# infra_stlink.net
KiCad netlist of a schematic drawn in Altium Designer
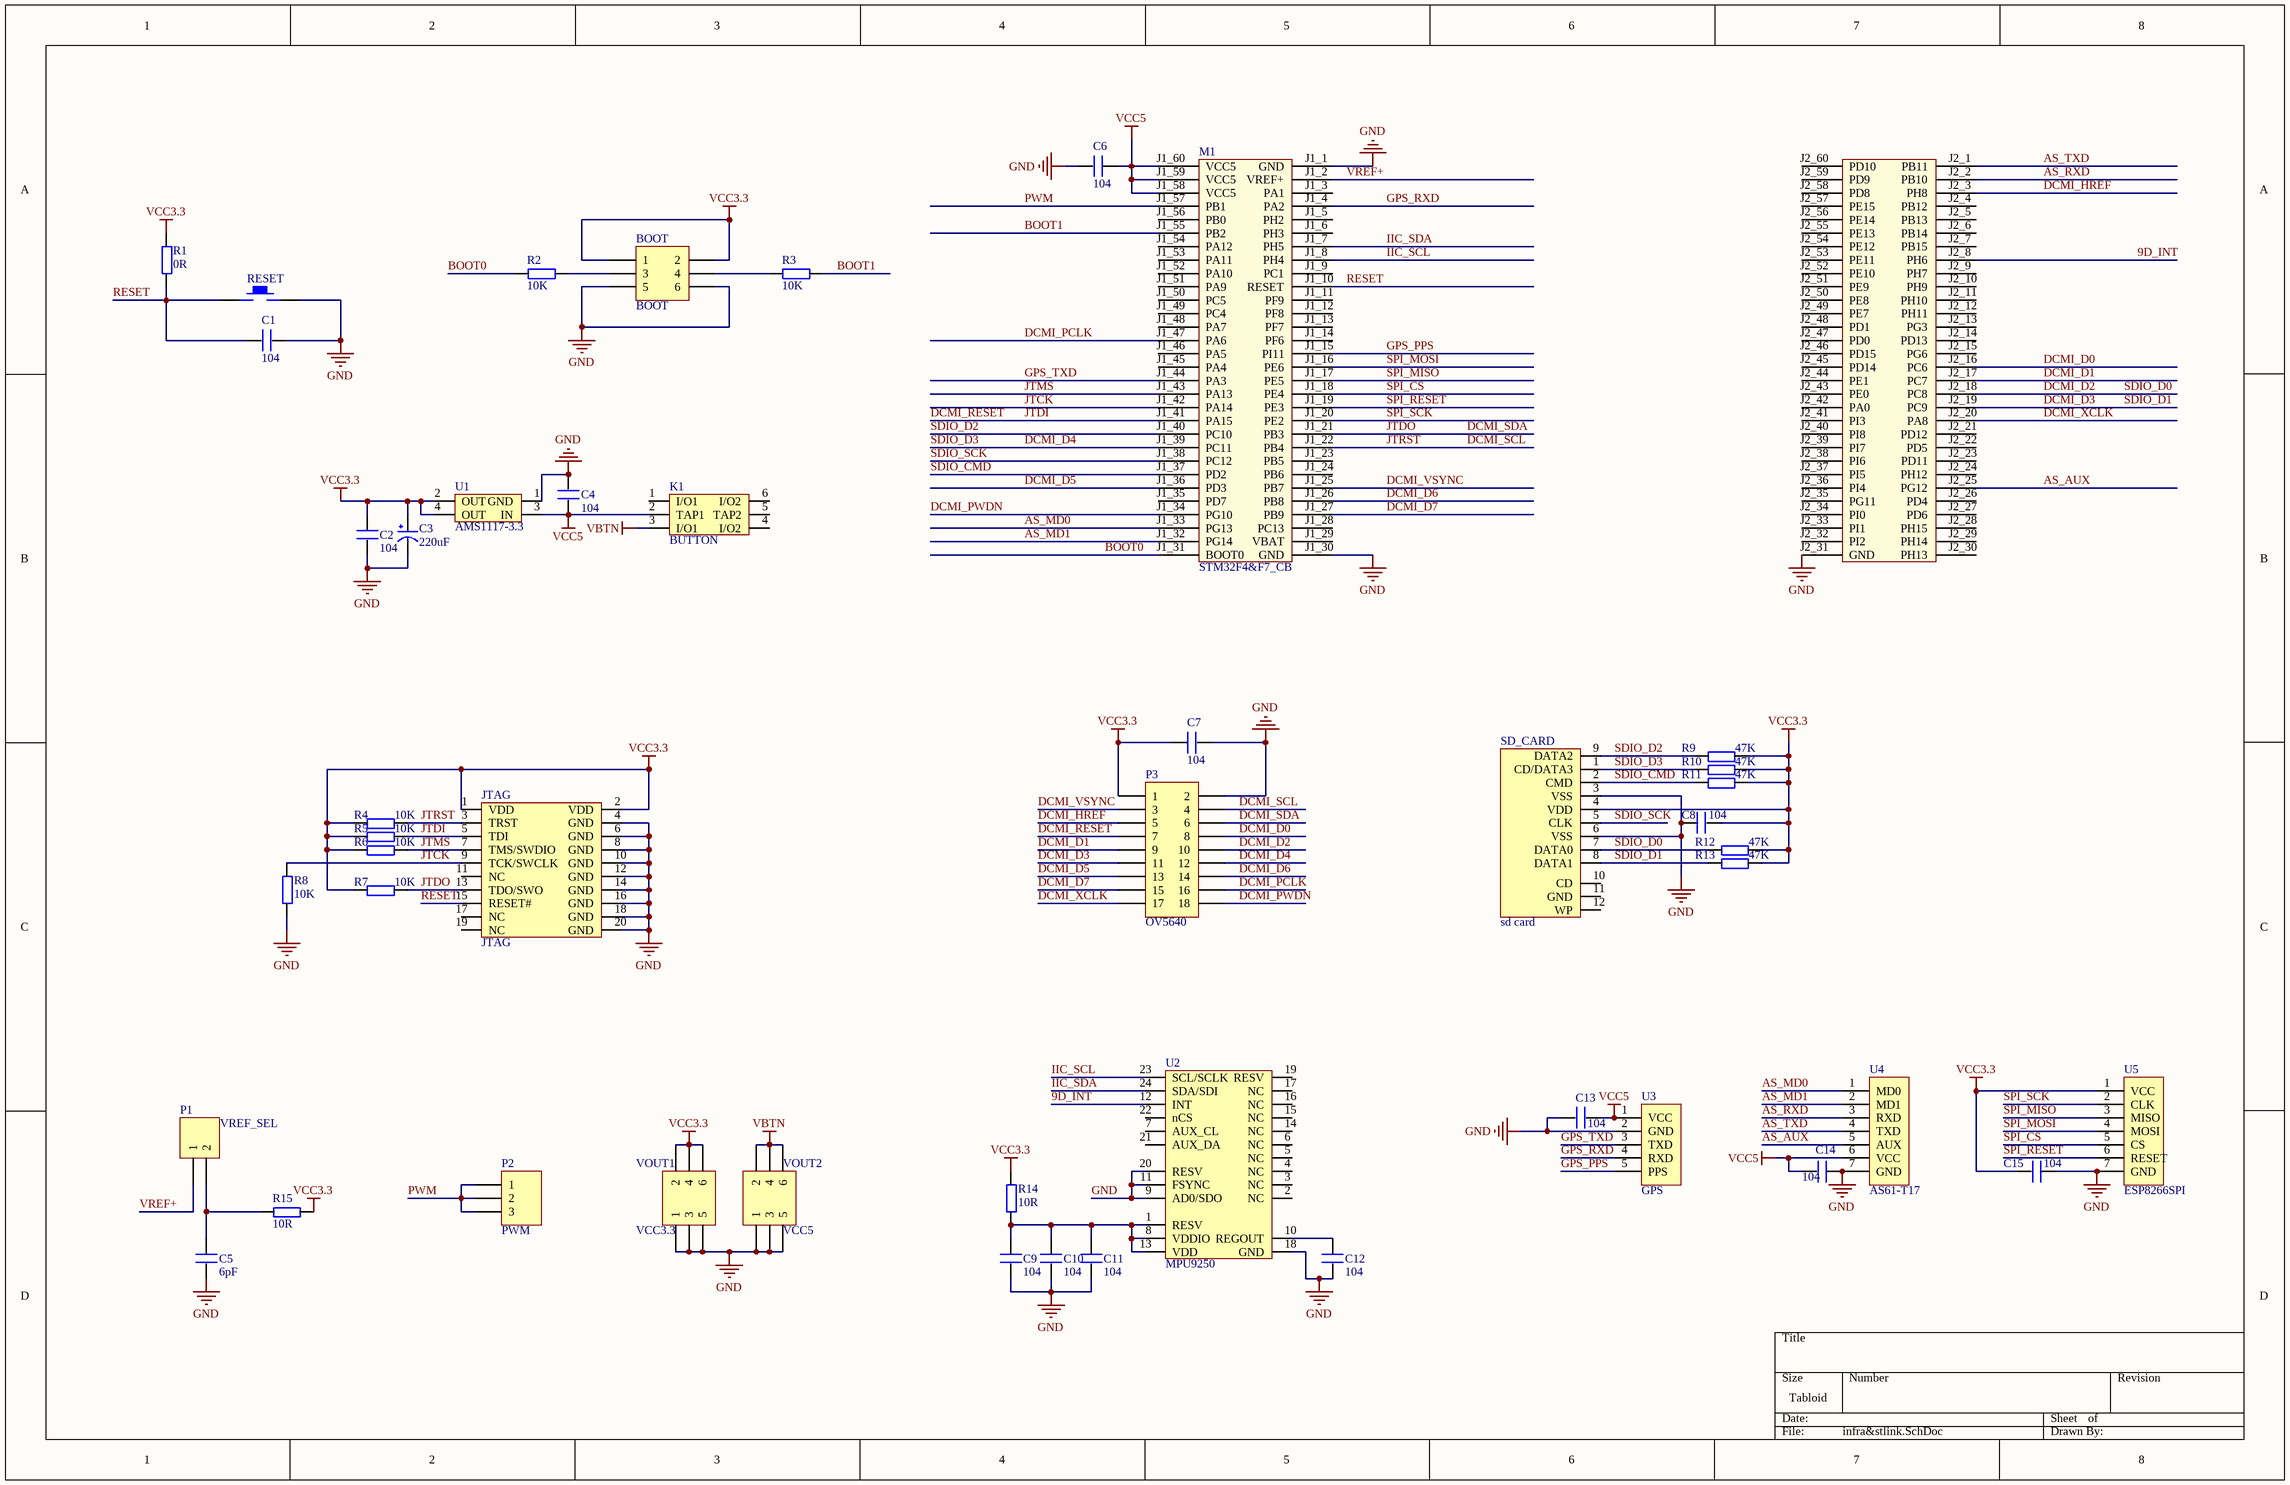
[diagram p0: infra&stlink.SchDoc]

(export (version "E")
  (design (tool "Eeschema 10.0.6"))
  (components
    (comp (ref "BOOT")
      (value "BOOT")
      (footprint "HDR2X3")
      (description "Header, 3-Pin, Dual row")
      (fields (field (name "PUBLISHER") "Altium Limited"))
      (libsource (lib "阿波罗STM32F4&F7底板封装库") (part "Header 3X2"))
    )
    (comp (ref "C1") (value "104") (footprint "0603P") (libsource (lib "阿波罗STM32F4&F7底板封装库") (part "C")))
    (comp (ref "C2") (value "104") (footprint "0805") (libsource (lib "阿波罗STM32F4&F7底板封装库") (part "C")))
    (comp (ref "C3")
      (value "220uF")
      (footprint "CC6.56.5")
      (libsource (lib "阿波罗STM32F4&F7底板封装库") (part "CAP"))
    )
    (comp (ref "C4") (value "104") (footprint "0805") (libsource (lib "阿波罗STM32F4&F7底板封装库") (part "C")))
    (comp (ref "C5") (value "6pF") (footprint "0805") (libsource (lib "STM32F767核心板封装库") (part "C")))
    (comp (ref "C6") (value "104") (footprint "0805") (libsource (lib "阿波罗STM32F4&F7底板封装库") (part "C")))
    (comp (ref "C7") (value "104") (footprint "0805") (libsource (lib "STM32F767核心板封装库") (part "C")))
    (comp (ref "C8") (value "104") (footprint "0805") (libsource (lib "阿波罗STM32F4&F7底板封装库") (part "C")))
    (comp (ref "C9") (value "104") (footprint "0805") (libsource (lib "阿波罗STM32F4&F7底板封装库") (part "C")))
    (comp (ref "C10") (value "104") (footprint "0805") (libsource (lib "阿波罗STM32F4&F7底板封装库") (part "C")))
    (comp (ref "C11") (value "104") (footprint "0805") (libsource (lib "阿波罗STM32F4&F7底板封装库") (part "C")))
    (comp (ref "C12") (value "104") (footprint "0805") (libsource (lib "阿波罗STM32F4&F7底板封装库") (part "C")))
    (comp (ref "C13") (value "104") (footprint "0805") (libsource (lib "阿波罗STM32F4&F7底板封装库") (part "C")))
    (comp (ref "C14") (value "104") (footprint "0805") (libsource (lib "阿波罗STM32F4&F7底板封装库") (part "C")))
    (comp (ref "C15") (value "104") (footprint "0805") (libsource (lib "阿波罗STM32F4&F7底板封装库") (part "C")))
    (comp (ref "JTAG")
      (value "JTAG")
      (footprint "JTAG_20")
      (libsource (lib "阿波罗STM32F4&F7底板封装库") (part "JTAG"))
    )
    (comp (ref "K1")
      (value "BUTTON")
      (footprint "BTN8.5*8.5")
      (libsource (lib "阿波罗STM32F4&F7底板封装库") (part "BUTTON"))
    )
    (comp (ref "M1")
      (value "STM32F4&F7_CB")
      (footprint "STM32F4&F7_CB")
      (description "F429/746 Core Board")
      (libsource (lib "阿波罗STM32F4&F7底板封装库") (part "STM32F4&F7_CB"))
    )
    (comp (ref "P1")
      (value "VREF_SEL")
      (footprint "HDR1X2")
      (description "Header, 2-Pin")
      (fields (field (name "PUBLISHER") "Altium Limited"))
      (libsource (lib "阿波罗STM32F4&F7底板封装库") (part "Header 2"))
    )
    (comp (ref "P2")
      (value "PWM")
      (footprint "HDR1X3")
      (description "Header, 3-Pin")
      (fields (field (name "PUBLISHER") "Altium Limited"))
      (libsource (lib "Miscellaneous Connectors") (part "Header 3"))
    )
    (comp (ref "P3")
      (value "OV5640")
      (footprint "HDR2X9")
      (description "Header, 9-Pin, Dual row")
      (fields (field (name "PUBLISHER") "Altium Limited"))
      (libsource (lib "阿波罗STM32F4&F7底板封装库") (part "Header 9X2"))
    )
    (comp (ref "R1") (value "0R") (footprint "0805") (libsource (lib "STM32F767核心板封装库") (part "R")))
    (comp (ref "R2") (value "10K") (footprint "0805") (libsource (lib "STM32F767核心板封装库") (part "R")))
    (comp (ref "R3") (value "10K") (footprint "0805") (libsource (lib "STM32F767核心板封装库") (part "R")))
    (comp (ref "R4") (value "10K") (footprint "0805") (libsource (lib "STM32F767核心板封装库") (part "R")))
    (comp (ref "R5") (value "10K") (footprint "0805") (libsource (lib "STM32F767核心板封装库") (part "R")))
    (comp (ref "R6") (value "10K") (footprint "0805") (libsource (lib "STM32F767核心板封装库") (part "R")))
    (comp (ref "R7") (value "10K") (footprint "0805") (libsource (lib "STM32F767核心板封装库") (part "R")))
    (comp (ref "R8") (value "10K") (footprint "0805") (libsource (lib "STM32F767核心板封装库") (part "R")))
    (comp (ref "R9") (value "47K") (footprint "0805") (libsource (lib "STM32F767核心板封装库") (part "R")))
    (comp (ref "R10") (value "47K") (footprint "0805") (libsource (lib "STM32F767核心板封装库") (part "R")))
    (comp (ref "R11") (value "47K") (footprint "0805") (libsource (lib "STM32F767核心板封装库") (part "R")))
    (comp (ref "R12") (value "47K") (footprint "0805") (libsource (lib "STM32F767核心板封装库") (part "R")))
    (comp (ref "R13") (value "47K") (footprint "0805") (libsource (lib "STM32F767核心板封装库") (part "R")))
    (comp (ref "R14") (value "10R") (footprint "0805") (libsource (lib "STM32F767核心板封装库") (part "R")))
    (comp (ref "R15") (value "10R") (footprint "0805") (libsource (lib "STM32F767核心板封装库") (part "R")))
    (comp (ref "RESET")
      (value "KEY_M")
      (footprint "KEY_M")
      (libsource (lib "阿波罗STM32F4&F7底板封装库") (part "KEY_M"))
    )
    (comp (ref "SD_CARD")
      (value "sd card")
      (footprint "SDCARD_L")
      (libsource (lib "阿波罗STM32F4&F7底板封装库") (part "sd card"))
    )
    (comp (ref "U1")
      (value "AMS1117-3.3")
      (footprint "AMS1117")
      (libsource (lib "阿波罗STM32F4&F7底板封装库") (part "AMS1117"))
    )
    (comp (ref "U2")
      (value "MPU9250")
      (footprint "QFN24-t")
      (description "9轴运动处理传感器")
      (libsource (lib "阿波罗STM32F4&F7底板封装库") (part "MPU9250"))
    )
    (comp (ref "U3")
      (value "GPS")
      (footprint "HDR1X5")
      (description "Header, 5-Pin")
      (fields (field (name "PUBLISHER") "Altium Limited"))
      (libsource (lib "Miscellaneous Connectors") (part "Header 5"))
    )
    (comp (ref "U4")
      (value "AS61-T17")
      (footprint "HDR1X7")
      (description "Header, 7-Pin")
      (fields (field (name "PUBLISHER") "Altium Limited"))
      (libsource (lib "Miscellaneous Connectors") (part "Header 7"))
    )
    (comp (ref "U5")
      (value "ESP8266SPI")
      (footprint "HDR1X7")
      (description "Header, 7-Pin")
      (fields (field (name "PUBLISHER") "Altium Limited"))
      (libsource (lib "Miscellaneous Connectors") (part "Header 7"))
    )
    (comp (ref "VOUT1")
      (value "VCC3.3")
      (footprint "HDR2X3")
      (description "Header, 3-Pin, Dual row")
      (fields (field (name "PUBLISHER") "Altium Limited"))
      (libsource (lib "Miscellaneous Connectors") (part "Header 3X2"))
    )
    (comp (ref "VOUT2")
      (value "VCC5")
      (footprint "HDR2X3")
      (description "Header, 3-Pin, Dual row")
      (fields (field (name "PUBLISHER") "Altium Limited"))
      (libsource (lib "Miscellaneous Connectors") (part "Header 3X2"))
    )
  )
  (nets
    (net (code "1") (name "/9D_INT") (class "Default")
      (node (ref "M1") (pin "J2_8") (pinfunction "PH6_J2_8") (pintype "passive"))
      (node (ref "U2") (pin "12") (pinfunction "INT_12") (pintype "passive"))
    )
    (net (code "2") (name "/AS_AUX") (class "Default")
      (node (ref "M1") (pin "J2_25") (pinfunction "PG12_J2_25") (pintype "passive"))
      (node (ref "U4") (pin "5") (pinfunction "CS_5") (pintype "passive"))
    )
    (net (code "3") (name "/AS_MD0") (class "Default")
      (node (ref "M1") (pin "J1_33") (pinfunction "PG13_J1_33") (pintype "passive"))
      (node (ref "U4") (pin "1") (pinfunction "VCC_1") (pintype "passive"))
    )
    (net (code "4") (name "/AS_MD1") (class "Default")
      (node (ref "M1") (pin "J1_32") (pinfunction "PG14_J1_32") (pintype "passive"))
      (node (ref "U4") (pin "2") (pinfunction "CLK_2") (pintype "passive"))
    )
    (net (code "5") (name "/AS_RXD") (class "Default")
      (node (ref "M1") (pin "J2_2") (pinfunction "PB10_J2_2") (pintype "passive"))
      (node (ref "U4") (pin "3") (pinfunction "MISO_3") (pintype "passive"))
    )
    (net (code "6") (name "/AS_TXD") (class "Default")
      (node (ref "M1") (pin "J2_1") (pinfunction "PB11_J2_1") (pintype "passive"))
      (node (ref "U4") (pin "4") (pinfunction "MOSI_4") (pintype "passive"))
    )
    (net (code "7") (name "/BOOT0") (class "Default")
      (node (ref "M1") (pin "J1_31") (pinfunction "BOOT0_J1_31") (pintype "passive"))
      (node (ref "R2") (pin "1") (pintype "passive"))
    )
    (net (code "8") (name "/BOOT1") (class "Default")
      (node (ref "M1") (pin "J1_55") (pinfunction "PB2_J1_55") (pintype "passive"))
      (node (ref "R3") (pin "2") (pintype "passive"))
    )
    (net (code "9") (name "/DCMI_D0") (class "Default")
      (node (ref "M1") (pin "J2_16") (pinfunction "PC6_J2_16") (pintype "passive"))
      (node (ref "P3") (pin "8") (pinfunction "8_8") (pintype "passive"))
    )
    (net (code "10") (name "/DCMI_D1") (class "Default")
      (node (ref "M1") (pin "J2_17") (pinfunction "PC7_J2_17") (pintype "passive"))
      (node (ref "P3") (pin "9") (pinfunction "9_9") (pintype "passive"))
    )
    (net (code "11") (name "/DCMI_D2") (class "Default")
      (node (ref "M1") (pin "J2_18") (pinfunction "PC8_J2_18") (pintype "passive"))
      (node (ref "P3") (pin "10") (pinfunction "10_10") (pintype "passive"))
      (node (ref "R12") (pin "1") (pintype "passive"))
      (node (ref "SD_CARD") (pin "7") (pinfunction "DATA0_7") (pintype "passive"))
    )
    (net (code "12") (name "/DCMI_D3") (class "Default")
      (node (ref "M1") (pin "J2_19") (pinfunction "PC9_J2_19") (pintype "passive"))
      (node (ref "P3") (pin "11") (pinfunction "11_11") (pintype "passive"))
      (node (ref "R13") (pin "1") (pintype "passive"))
      (node (ref "SD_CARD") (pin "8") (pinfunction "DATA1_8") (pintype "passive"))
    )
    (net (code "13") (name "/DCMI_D4") (class "Default")
      (node (ref "M1") (pin "J1_39") (pinfunction "PC11_J1_39") (pintype "passive"))
      (node (ref "P3") (pin "12") (pinfunction "12_12") (pintype "passive"))
      (node (ref "R10") (pin "1") (pintype "passive"))
      (node (ref "SD_CARD") (pin "1") (pinfunction "CD/DATA3_1") (pintype "passive"))
    )
    (net (code "14") (name "/DCMI_D5") (class "Default")
      (node (ref "M1") (pin "J1_36") (pinfunction "PD3_J1_36") (pintype "passive"))
      (node (ref "P3") (pin "13") (pinfunction "13_13") (pintype "passive"))
    )
    (net (code "15") (name "/DCMI_D6") (class "Default")
      (node (ref "M1") (pin "J1_26") (pinfunction "PB8_J1_26") (pintype "passive"))
      (node (ref "P3") (pin "14") (pinfunction "14_14") (pintype "passive"))
    )
    (net (code "16") (name "/DCMI_D7") (class "Default")
      (node (ref "M1") (pin "J1_27") (pinfunction "PB9_J1_27") (pintype "passive"))
      (node (ref "P3") (pin "15") (pinfunction "15_15") (pintype "passive"))
    )
    (net (code "17") (name "/DCMI_HREF") (class "Default")
      (node (ref "M1") (pin "J2_3") (pinfunction "PH8_J2_3") (pintype "passive"))
      (node (ref "P3") (pin "5") (pinfunction "5_5") (pintype "passive"))
    )
    (net (code "18") (name "/DCMI_PCLK") (class "Default")
      (node (ref "M1") (pin "J1_47") (pinfunction "PA6_J1_47") (pintype "passive"))
      (node (ref "P3") (pin "16") (pinfunction "16_16") (pintype "passive"))
    )
    (net (code "19") (name "/DCMI_PWDN") (class "Default")
      (node (ref "M1") (pin "J1_34") (pinfunction "PG10_J1_34") (pintype "passive"))
      (node (ref "P3") (pin "18") (pinfunction "18_18") (pintype "passive"))
    )
    (net (code "20") (name "/DCMI_RESET") (class "Default")
      (node (ref "JTAG") (pin "5") (pinfunction "TDI_5") (pintype "passive"))
      (node (ref "M1") (pin "J1_41") (pinfunction "PA15_J1_41") (pintype "passive"))
      (node (ref "P3") (pin "7") (pinfunction "7_7") (pintype "passive"))
      (node (ref "R5") (pin "2") (pintype "passive"))
    )
    (net (code "21") (name "/DCMI_SCL") (class "Default")
      (node (ref "JTAG") (pin "3") (pinfunction "TRST_3") (pintype "passive"))
      (node (ref "M1") (pin "J1_22") (pinfunction "PB4_J1_22") (pintype "passive"))
      (node (ref "P3") (pin "4") (pinfunction "4_4") (pintype "passive"))
      (node (ref "R4") (pin "2") (pintype "passive"))
    )
    (net (code "22") (name "/DCMI_SDA") (class "Default")
      (node (ref "JTAG") (pin "13") (pinfunction "TDO/SWO_13") (pintype "passive"))
      (node (ref "M1") (pin "J1_21") (pinfunction "PB3_J1_21") (pintype "passive"))
      (node (ref "P3") (pin "6") (pinfunction "6_6") (pintype "passive"))
      (node (ref "R7") (pin "2") (pintype "passive"))
    )
    (net (code "23") (name "/DCMI_VSYNC") (class "Default")
      (node (ref "M1") (pin "J1_25") (pinfunction "PB7_J1_25") (pintype "passive"))
      (node (ref "P3") (pin "3") (pinfunction "3_3") (pintype "passive"))
    )
    (net (code "24") (name "/DCMI_XCLK") (class "Default")
      (node (ref "M1") (pin "J2_20") (pinfunction "PA8_J2_20") (pintype "passive"))
      (node (ref "P3") (pin "17") (pinfunction "17_17") (pintype "passive"))
    )
    (net (code "25") (name "/GPS_PPS") (class "Default")
      (node (ref "M1") (pin "J1_15") (pinfunction "PI11_J1_15") (pintype "passive"))
      (node (ref "U3") (pin "5") (pinfunction "PPS_5") (pintype "passive"))
    )
    (net (code "26") (name "/GPS_RXD") (class "Default")
      (node (ref "M1") (pin "J1_4") (pinfunction "PA2_J1_4") (pintype "passive"))
      (node (ref "U3") (pin "4") (pinfunction "RXD_4") (pintype "passive"))
    )
    (net (code "27") (name "/GPS_TXD") (class "Default")
      (node (ref "M1") (pin "J1_44") (pinfunction "PA3_J1_44") (pintype "passive"))
      (node (ref "U3") (pin "3") (pinfunction "TXD_3") (pintype "passive"))
    )
    (net (code "28") (name "/IIC_SCL") (class "Default")
      (node (ref "M1") (pin "J1_8") (pinfunction "PH4_J1_8") (pintype "passive"))
      (node (ref "U2") (pin "23") (pinfunction "SCL/SCLK_23") (pintype "passive"))
    )
    (net (code "29") (name "/IIC_SDA") (class "Default")
      (node (ref "M1") (pin "J1_7") (pinfunction "PH5_J1_7") (pintype "passive"))
      (node (ref "U2") (pin "24") (pinfunction "SDA/SDI_24") (pintype "passive"))
    )
    (net (code "30") (name "/JTCK") (class "Default")
      (node (ref "JTAG") (pin "9") (pinfunction "TCK/SWCLK_9") (pintype "passive"))
      (node (ref "M1") (pin "J1_42") (pinfunction "PA14_J1_42") (pintype "passive"))
      (node (ref "R8") (pin "2") (pintype "passive"))
    )
    (net (code "31") (name "/JTMS") (class "Default")
      (node (ref "JTAG") (pin "7") (pinfunction "TMS/SWDIO_7") (pintype "passive"))
      (node (ref "M1") (pin "J1_43") (pinfunction "PA13_J1_43") (pintype "passive"))
      (node (ref "R6") (pin "2") (pintype "passive"))
    )
    (net (code "32") (name "/PWM") (class "Default")
      (node (ref "M1") (pin "J1_57") (pinfunction "PB1_J1_57") (pintype "passive"))
      (node (ref "P2") (pin "1") (pinfunction "1_1") (pintype "passive"))
      (node (ref "P2") (pin "2") (pinfunction "2_2") (pintype "passive"))
      (node (ref "P2") (pin "3") (pinfunction "3_3") (pintype "passive"))
    )
    (net (code "33") (name "/RESET") (class "Default")
      (node (ref "C1") (pin "1") (pintype "passive"))
      (node (ref "JTAG") (pin "15") (pinfunction "RESET#_15") (pintype "passive"))
      (node (ref "M1") (pin "J1_10") (pinfunction "RESET_J1_10") (pintype "passive"))
      (node (ref "R1") (pin "1") (pintype "passive"))
      (node (ref "RESET") (pin "1") (pinfunction "1_1") (pintype "passive"))
    )
    (net (code "34") (name "/SDIO_CMD") (class "Default")
      (node (ref "M1") (pin "J1_37") (pinfunction "PD2_J1_37") (pintype "passive"))
      (node (ref "R11") (pin "1") (pintype "passive"))
      (node (ref "SD_CARD") (pin "2") (pinfunction "CMD_2") (pintype "passive"))
    )
    (net (code "35") (name "/SDIO_D2") (class "Default")
      (node (ref "M1") (pin "J1_40") (pinfunction "PC10_J1_40") (pintype "passive"))
      (node (ref "R9") (pin "1") (pintype "passive"))
      (node (ref "SD_CARD") (pin "9") (pinfunction "DATA2_9") (pintype "passive"))
    )
    (net (code "36") (name "/SDIO_SCK") (class "Default")
      (node (ref "M1") (pin "J1_38") (pinfunction "PC12_J1_38") (pintype "passive"))
      (node (ref "SD_CARD") (pin "5") (pinfunction "CLK_5") (pintype "passive"))
    )
    (net (code "37") (name "/SPI_CS") (class "Default")
      (node (ref "M1") (pin "J1_18") (pinfunction "PE4_J1_18") (pintype "passive"))
      (node (ref "U5") (pin "5") (pinfunction "CS_5") (pintype "passive"))
    )
    (net (code "38") (name "/SPI_MISO") (class "Default")
      (node (ref "M1") (pin "J1_17") (pinfunction "PE5_J1_17") (pintype "passive"))
      (node (ref "U5") (pin "3") (pinfunction "MISO_3") (pintype "passive"))
    )
    (net (code "39") (name "/SPI_MOSI") (class "Default")
      (node (ref "M1") (pin "J1_16") (pinfunction "PE6_J1_16") (pintype "passive"))
      (node (ref "U5") (pin "4") (pinfunction "MOSI_4") (pintype "passive"))
    )
    (net (code "40") (name "/SPI_RESET") (class "Default")
      (node (ref "M1") (pin "J1_19") (pinfunction "PE3_J1_19") (pintype "passive"))
      (node (ref "U5") (pin "6") (pinfunction "RESET_6") (pintype "passive"))
    )
    (net (code "41") (name "/SPI_SCK") (class "Default")
      (node (ref "M1") (pin "J1_20") (pinfunction "PE2_J1_20") (pintype "passive"))
      (node (ref "U5") (pin "2") (pinfunction "CLK_2") (pintype "passive"))
    )
    (net (code "42") (name "/VREF+") (class "Default")
      (node (ref "M1") (pin "J1_2") (pinfunction "VREF+_J1_2") (pintype "passive"))
      (node (ref "P1") (pin "1") (pinfunction "1_1") (pintype "passive"))
    )
    (net (code "43") (name "GND") (class "Default")
      (node (ref "BOOT") (pin "5") (pinfunction "5_5") (pintype "passive"))
      (node (ref "BOOT") (pin "6") (pinfunction "6_6") (pintype "passive"))
      (node (ref "C1") (pin "2") (pintype "passive"))
      (node (ref "C10") (pin "1") (pintype "passive"))
      (node (ref "C11") (pin "1") (pintype "passive"))
      (node (ref "C12") (pin "1") (pintype "passive"))
      (node (ref "C13") (pin "1") (pintype "passive"))
      (node (ref "C14") (pin "1") (pintype "passive"))
      (node (ref "C15") (pin "2") (pintype "passive"))
      (node (ref "C2") (pin "1") (pintype "passive"))
      (node (ref "C3") (pin "2") (pinfunction "GND_2") (pintype "passive"))
      (node (ref "C4") (pin "2") (pintype "passive"))
      (node (ref "C5") (pin "1") (pintype "passive"))
      (node (ref "C6") (pin "1") (pintype "passive"))
      (node (ref "C7") (pin "2") (pintype "passive"))
      (node (ref "C8") (pin "1") (pintype "passive"))
      (node (ref "C9") (pin "1") (pintype "passive"))
      (node (ref "JTAG") (pin "10") (pinfunction "GND_10") (pintype "passive"))
      (node (ref "JTAG") (pin "12") (pinfunction "GND_12") (pintype "passive"))
      (node (ref "JTAG") (pin "14") (pinfunction "GND_14") (pintype "passive"))
      (node (ref "JTAG") (pin "16") (pinfunction "GND_16") (pintype "passive"))
      (node (ref "JTAG") (pin "18") (pinfunction "GND_18") (pintype "passive"))
      (node (ref "JTAG") (pin "20") (pinfunction "GND_20") (pintype "passive"))
      (node (ref "JTAG") (pin "4") (pinfunction "GND_4") (pintype "passive"))
      (node (ref "JTAG") (pin "6") (pinfunction "GND_6") (pintype "passive"))
      (node (ref "JTAG") (pin "8") (pinfunction "GND_8") (pintype "passive"))
      (node (ref "M1") (pin "J1_1") (pinfunction "GND_J1_1") (pintype "passive"))
      (node (ref "M1") (pin "J1_30") (pinfunction "GND_J1_30") (pintype "passive"))
      (node (ref "M1") (pin "J2_31") (pinfunction "GND_J2_31") (pintype "passive"))
      (node (ref "P3") (pin "2") (pinfunction "2_2") (pintype "passive"))
      (node (ref "R8") (pin "1") (pintype "passive"))
      (node (ref "RESET") (pin "2") (pinfunction "2_2") (pintype "passive"))
      (node (ref "SD_CARD") (pin "3") (pinfunction "VSS_3") (pintype "passive"))
      (node (ref "SD_CARD") (pin "6") (pinfunction "VSS_6") (pintype "passive"))
      (node (ref "U1") (pin "1") (pinfunction "GND_1") (pintype "passive"))
      (node (ref "U2") (pin "11") (pinfunction "FSYNC_11") (pintype "passive"))
      (node (ref "U2") (pin "18") (pinfunction "GND_18") (pintype "passive"))
      (node (ref "U2") (pin "20") (pinfunction "RESV_20") (pintype "passive"))
      (node (ref "U2") (pin "9") (pinfunction "AD0/SDO_9") (pintype "passive"))
      (node (ref "U3") (pin "2") (pinfunction "GND_2") (pintype "passive"))
      (node (ref "U4") (pin "7") (pinfunction "GND_7") (pintype "passive"))
      (node (ref "U5") (pin "7") (pinfunction "GND_7") (pintype "passive"))
      (node (ref "VOUT1") (pin "1") (pinfunction "1_1") (pintype "passive"))
      (node (ref "VOUT1") (pin "3") (pinfunction "3_3") (pintype "passive"))
      (node (ref "VOUT1") (pin "5") (pinfunction "5_5") (pintype "passive"))
      (node (ref "VOUT2") (pin "1") (pinfunction "1_1") (pintype "passive"))
      (node (ref "VOUT2") (pin "3") (pinfunction "3_3") (pintype "passive"))
      (node (ref "VOUT2") (pin "5") (pinfunction "5_5") (pintype "passive"))
    )
    (net (code "44") (name "Net-(BOOT-Pad3)") (class "Default")
      (node (ref "BOOT") (pin "3") (pinfunction "3_3") (pintype "passive"))
      (node (ref "R2") (pin "2") (pintype "passive"))
    )
    (net (code "45") (name "Net-(BOOT-Pad4)") (class "Default")
      (node (ref "BOOT") (pin "4") (pinfunction "4_4") (pintype "passive"))
      (node (ref "R3") (pin "1") (pintype "passive"))
    )
    (net (code "46") (name "Net-(C5-Pad2)") (class "Default")
      (node (ref "C5") (pin "2") (pintype "passive"))
      (node (ref "P1") (pin "2") (pinfunction "2_2") (pintype "passive"))
      (node (ref "R15") (pin "1") (pintype "passive"))
    )
    (net (code "47") (name "Net-(U2-REGOUT)") (class "Default")
      (node (ref "C12") (pin "2") (pintype "passive"))
      (node (ref "U2") (pin "10") (pinfunction "REGOUT_10") (pintype "passive"))
    )
    (net (code "48") (name "Net-(U2-VDD)") (class "Default")
      (node (ref "C10") (pin "2") (pintype "passive"))
      (node (ref "C11") (pin "2") (pintype "passive"))
      (node (ref "C9") (pin "2") (pintype "passive"))
      (node (ref "R14") (pin "1") (pintype "passive"))
      (node (ref "U2") (pin "1") (pinfunction "RESV_1") (pintype "passive"))
      (node (ref "U2") (pin "13") (pinfunction "VDD_13") (pintype "passive"))
      (node (ref "U2") (pin "8") (pinfunction "VDDIO_8") (pintype "passive"))
    )
    (net (code "49") (name "VBTN") (class "Default")
      (node (ref "K1") (pin "3") (pinfunction "I/O1_3") (pintype "passive"))
      (node (ref "VOUT2") (pin "2") (pinfunction "2_2") (pintype "passive"))
      (node (ref "VOUT2") (pin "4") (pinfunction "4_4") (pintype "passive"))
      (node (ref "VOUT2") (pin "6") (pinfunction "6_6") (pintype "passive"))
    )
    (net (code "50") (name "VCC3.3") (class "Default")
      (node (ref "BOOT") (pin "1") (pinfunction "1_1") (pintype "passive"))
      (node (ref "BOOT") (pin "2") (pinfunction "2_2") (pintype "passive"))
      (node (ref "C15") (pin "1") (pintype "passive"))
      (node (ref "C2") (pin "2") (pintype "passive"))
      (node (ref "C3") (pin "1") (pinfunction "VCC_1") (pintype "passive"))
      (node (ref "C7") (pin "1") (pintype "passive"))
      (node (ref "C8") (pin "2") (pintype "passive"))
      (node (ref "JTAG") (pin "1") (pinfunction "VDD_1") (pintype "passive"))
      (node (ref "JTAG") (pin "2") (pinfunction "VDD_2") (pintype "passive"))
      (node (ref "P3") (pin "1") (pinfunction "1_1") (pintype "passive"))
      (node (ref "R1") (pin "2") (pintype "passive"))
      (node (ref "R10") (pin "2") (pintype "passive"))
      (node (ref "R11") (pin "2") (pintype "passive"))
      (node (ref "R12") (pin "2") (pintype "passive"))
      (node (ref "R13") (pin "2") (pintype "passive"))
      (node (ref "R14") (pin "2") (pintype "passive"))
      (node (ref "R15") (pin "2") (pintype "passive"))
      (node (ref "R4") (pin "1") (pintype "passive"))
      (node (ref "R5") (pin "1") (pintype "passive"))
      (node (ref "R6") (pin "1") (pintype "passive"))
      (node (ref "R7") (pin "1") (pintype "passive"))
      (node (ref "R9") (pin "2") (pintype "passive"))
      (node (ref "SD_CARD") (pin "4") (pinfunction "VDD_4") (pintype "passive"))
      (node (ref "U1") (pin "2") (pinfunction "OUT_2") (pintype "passive"))
      (node (ref "U1") (pin "4") (pinfunction "OUT_4") (pintype "passive"))
      (node (ref "U5") (pin "1") (pinfunction "VCC_1") (pintype "passive"))
      (node (ref "VOUT1") (pin "2") (pinfunction "2_2") (pintype "passive"))
      (node (ref "VOUT1") (pin "4") (pinfunction "4_4") (pintype "passive"))
      (node (ref "VOUT1") (pin "6") (pinfunction "6_6") (pintype "passive"))
    )
    (net (code "51") (name "VCC5") (class "Default")
      (node (ref "C13") (pin "2") (pintype "passive"))
      (node (ref "C14") (pin "2") (pintype "passive"))
      (node (ref "C4") (pin "1") (pintype "passive"))
      (node (ref "C6") (pin "2") (pintype "passive"))
      (node (ref "K1") (pin "2") (pinfunction "TAP1_2") (pintype "passive"))
      (node (ref "M1") (pin "J1_58") (pinfunction "VCC5_J1_58") (pintype "passive"))
      (node (ref "M1") (pin "J1_59") (pinfunction "VCC5_J1_59") (pintype "passive"))
      (node (ref "M1") (pin "J1_60") (pinfunction "VCC5_J1_60") (pintype "passive"))
      (node (ref "U1") (pin "3") (pinfunction "IN_3") (pintype "passive"))
      (node (ref "U3") (pin "1") (pinfunction "VCC_1") (pintype "passive"))
      (node (ref "U4") (pin "6") (pinfunction "RESET_6") (pintype "passive"))
    )
    (net (code "52") (name "unconnected-(JTAG-NC-Pad11)") (class "Default")
      (node (ref "JTAG") (pin "11") (pinfunction "NC_11") (pintype "passive"))
    )
    (net (code "53") (name "unconnected-(JTAG-NC-Pad17)") (class "Default")
      (node (ref "JTAG") (pin "17") (pinfunction "NC_17") (pintype "passive"))
    )
    (net (code "54") (name "unconnected-(JTAG-NC-Pad19)") (class "Default")
      (node (ref "JTAG") (pin "19") (pinfunction "NC_19") (pintype "passive"))
    )
    (net (code "55") (name "unconnected-(K1-I{slash}O1-Pad1)") (class "Default")
      (node (ref "K1") (pin "1") (pinfunction "I/O1_1") (pintype "passive"))
    )
    (net (code "56") (name "unconnected-(K1-I{slash}O2-Pad4)") (class "Default")
      (node (ref "K1") (pin "4") (pinfunction "I/O2_4") (pintype "passive"))
    )
    (net (code "57") (name "unconnected-(K1-I{slash}O2-Pad6)") (class "Default")
      (node (ref "K1") (pin "6") (pinfunction "I/O2_6") (pintype "passive"))
    )
    (net (code "58") (name "unconnected-(K1-TAP2-Pad5)") (class "Default")
      (node (ref "K1") (pin "5") (pinfunction "TAP2_5") (pintype "passive"))
    )
    (net (code "59") (name "unconnected-(M1-PA0-PadJ2_42)") (class "Default")
      (node (ref "M1") (pin "J2_42") (pinfunction "PA0_J2_42") (pintype "passive"))
    )
    (net (code "60") (name "unconnected-(M1-PA1-PadJ1_3)") (class "Default")
      (node (ref "M1") (pin "J1_3") (pinfunction "PA1_J1_3") (pintype "passive"))
    )
    (net (code "61") (name "unconnected-(M1-PA4-PadJ1_45)") (class "Default")
      (node (ref "M1") (pin "J1_45") (pinfunction "PA4_J1_45") (pintype "passive"))
    )
    (net (code "62") (name "unconnected-(M1-PA5-PadJ1_46)") (class "Default")
      (node (ref "M1") (pin "J1_46") (pinfunction "PA5_J1_46") (pintype "passive"))
    )
    (net (code "63") (name "unconnected-(M1-PA7-PadJ1_48)") (class "Default")
      (node (ref "M1") (pin "J1_48") (pinfunction "PA7_J1_48") (pintype "passive"))
    )
    (net (code "64") (name "unconnected-(M1-PA9-PadJ1_51)") (class "Default")
      (node (ref "M1") (pin "J1_51") (pinfunction "PA9_J1_51") (pintype "passive"))
    )
    (net (code "65") (name "unconnected-(M1-PA10-PadJ1_52)") (class "Default")
      (node (ref "M1") (pin "J1_52") (pinfunction "PA10_J1_52") (pintype "passive"))
    )
    (net (code "66") (name "unconnected-(M1-PA11-PadJ1_53)") (class "Default")
      (node (ref "M1") (pin "J1_53") (pinfunction "PA11_J1_53") (pintype "passive"))
    )
    (net (code "67") (name "unconnected-(M1-PA12-PadJ1_54)") (class "Default")
      (node (ref "M1") (pin "J1_54") (pinfunction "PA12_J1_54") (pintype "passive"))
    )
    (net (code "68") (name "unconnected-(M1-PB0-PadJ1_56)") (class "Default")
      (node (ref "M1") (pin "J1_56") (pinfunction "PB0_J1_56") (pintype "passive"))
    )
    (net (code "69") (name "unconnected-(M1-PB5-PadJ1_23)") (class "Default")
      (node (ref "M1") (pin "J1_23") (pinfunction "PB5_J1_23") (pintype "passive"))
    )
    (net (code "70") (name "unconnected-(M1-PB6-PadJ1_24)") (class "Default")
      (node (ref "M1") (pin "J1_24") (pinfunction "PB6_J1_24") (pintype "passive"))
    )
    (net (code "71") (name "unconnected-(M1-PB12-PadJ2_4)") (class "Default")
      (node (ref "M1") (pin "J2_4") (pinfunction "PB12_J2_4") (pintype "passive"))
    )
    (net (code "72") (name "unconnected-(M1-PB13-PadJ2_5)") (class "Default")
      (node (ref "M1") (pin "J2_5") (pinfunction "PB13_J2_5") (pintype "passive"))
    )
    (net (code "73") (name "unconnected-(M1-PB14-PadJ2_6)") (class "Default")
      (node (ref "M1") (pin "J2_6") (pinfunction "PB14_J2_6") (pintype "passive"))
    )
    (net (code "74") (name "unconnected-(M1-PB15-PadJ2_7)") (class "Default")
      (node (ref "M1") (pin "J2_7") (pinfunction "PB15_J2_7") (pintype "passive"))
    )
    (net (code "75") (name "unconnected-(M1-PC1-PadJ1_9)") (class "Default")
      (node (ref "M1") (pin "J1_9") (pinfunction "PC1_J1_9") (pintype "passive"))
    )
    (net (code "76") (name "unconnected-(M1-PC4-PadJ1_49)") (class "Default")
      (node (ref "M1") (pin "J1_49") (pinfunction "PC4_J1_49") (pintype "passive"))
    )
    (net (code "77") (name "unconnected-(M1-PC5-PadJ1_50)") (class "Default")
      (node (ref "M1") (pin "J1_50") (pinfunction "PC5_J1_50") (pintype "passive"))
    )
    (net (code "78") (name "unconnected-(M1-PC13-PadJ1_28)") (class "Default")
      (node (ref "M1") (pin "J1_28") (pinfunction "PC13_J1_28") (pintype "passive"))
    )
    (net (code "79") (name "unconnected-(M1-PD0-PadJ2_47)") (class "Default")
      (node (ref "M1") (pin "J2_47") (pinfunction "PD0_J2_47") (pintype "passive"))
    )
    (net (code "80") (name "unconnected-(M1-PD1-PadJ2_48)") (class "Default")
      (node (ref "M1") (pin "J2_48") (pinfunction "PD1_J2_48") (pintype "passive"))
    )
    (net (code "81") (name "unconnected-(M1-PD4-PadJ2_26)") (class "Default")
      (node (ref "M1") (pin "J2_26") (pinfunction "PD4_J2_26") (pintype "passive"))
    )
    (net (code "82") (name "unconnected-(M1-PD5-PadJ2_22)") (class "Default")
      (node (ref "M1") (pin "J2_22") (pinfunction "PD5_J2_22") (pintype "passive"))
    )
    (net (code "83") (name "unconnected-(M1-PD6-PadJ2_27)") (class "Default")
      (node (ref "M1") (pin "J2_27") (pinfunction "PD6_J2_27") (pintype "passive"))
    )
    (net (code "84") (name "unconnected-(M1-PD7-PadJ1_35)") (class "Default")
      (node (ref "M1") (pin "J1_35") (pinfunction "PD7_J1_35") (pintype "passive"))
    )
    (net (code "85") (name "unconnected-(M1-PD8-PadJ2_58)") (class "Default")
      (node (ref "M1") (pin "J2_58") (pinfunction "PD8_J2_58") (pintype "passive"))
    )
    (net (code "86") (name "unconnected-(M1-PD9-PadJ2_59)") (class "Default")
      (node (ref "M1") (pin "J2_59") (pinfunction "PD9_J2_59") (pintype "passive"))
    )
    (net (code "87") (name "unconnected-(M1-PD10-PadJ2_60)") (class "Default")
      (node (ref "M1") (pin "J2_60") (pinfunction "PD10_J2_60") (pintype "passive"))
    )
    (net (code "88") (name "unconnected-(M1-PD11-PadJ2_23)") (class "Default")
      (node (ref "M1") (pin "J2_23") (pinfunction "PD11_J2_23") (pintype "passive"))
    )
    (net (code "89") (name "unconnected-(M1-PD12-PadJ2_21)") (class "Default")
      (node (ref "M1") (pin "J2_21") (pinfunction "PD12_J2_21") (pintype "passive"))
    )
    (net (code "90") (name "unconnected-(M1-PD13-PadJ2_14)") (class "Default")
      (node (ref "M1") (pin "J2_14") (pinfunction "PD13_J2_14") (pintype "passive"))
    )
    (net (code "91") (name "unconnected-(M1-PD14-PadJ2_45)") (class "Default")
      (node (ref "M1") (pin "J2_45") (pinfunction "PD14_J2_45") (pintype "passive"))
    )
    (net (code "92") (name "unconnected-(M1-PD15-PadJ2_46)") (class "Default")
      (node (ref "M1") (pin "J2_46") (pinfunction "PD15_J2_46") (pintype "passive"))
    )
    (net (code "93") (name "unconnected-(M1-PE0-PadJ2_43)") (class "Default")
      (node (ref "M1") (pin "J2_43") (pinfunction "PE0_J2_43") (pintype "passive"))
    )
    (net (code "94") (name "unconnected-(M1-PE1-PadJ2_44)") (class "Default")
      (node (ref "M1") (pin "J2_44") (pinfunction "PE1_J2_44") (pintype "passive"))
    )
    (net (code "95") (name "unconnected-(M1-PE7-PadJ2_49)") (class "Default")
      (node (ref "M1") (pin "J2_49") (pinfunction "PE7_J2_49") (pintype "passive"))
    )
    (net (code "96") (name "unconnected-(M1-PE8-PadJ2_50)") (class "Default")
      (node (ref "M1") (pin "J2_50") (pinfunction "PE8_J2_50") (pintype "passive"))
    )
    (net (code "97") (name "unconnected-(M1-PE9-PadJ2_51)") (class "Default")
      (node (ref "M1") (pin "J2_51") (pinfunction "PE9_J2_51") (pintype "passive"))
    )
    (net (code "98") (name "unconnected-(M1-PE10-PadJ2_52)") (class "Default")
      (node (ref "M1") (pin "J2_52") (pinfunction "PE10_J2_52") (pintype "passive"))
    )
    (net (code "99") (name "unconnected-(M1-PE11-PadJ2_53)") (class "Default")
      (node (ref "M1") (pin "J2_53") (pinfunction "PE11_J2_53") (pintype "passive"))
    )
    (net (code "100") (name "unconnected-(M1-PE12-PadJ2_54)") (class "Default")
      (node (ref "M1") (pin "J2_54") (pinfunction "PE12_J2_54") (pintype "passive"))
    )
    (net (code "101") (name "unconnected-(M1-PE13-PadJ2_55)") (class "Default")
      (node (ref "M1") (pin "J2_55") (pinfunction "PE13_J2_55") (pintype "passive"))
    )
    (net (code "102") (name "unconnected-(M1-PE14-PadJ2_56)") (class "Default")
      (node (ref "M1") (pin "J2_56") (pinfunction "PE14_J2_56") (pintype "passive"))
    )
    (net (code "103") (name "unconnected-(M1-PE15-PadJ2_57)") (class "Default")
      (node (ref "M1") (pin "J2_57") (pinfunction "PE15_J2_57") (pintype "passive"))
    )
    (net (code "104") (name "unconnected-(M1-PF6-PadJ1_14)") (class "Default")
      (node (ref "M1") (pin "J1_14") (pinfunction "PF6_J1_14") (pintype "passive"))
    )
    (net (code "105") (name "unconnected-(M1-PF7-PadJ1_13)") (class "Default")
      (node (ref "M1") (pin "J1_13") (pinfunction "PF7_J1_13") (pintype "passive"))
    )
    (net (code "106") (name "unconnected-(M1-PF8-PadJ1_12)") (class "Default")
      (node (ref "M1") (pin "J1_12") (pinfunction "PF8_J1_12") (pintype "passive"))
    )
    (net (code "107") (name "unconnected-(M1-PF9-PadJ1_11)") (class "Default")
      (node (ref "M1") (pin "J1_11") (pinfunction "PF9_J1_11") (pintype "passive"))
    )
    (net (code "108") (name "unconnected-(M1-PG3-PadJ2_13)") (class "Default")
      (node (ref "M1") (pin "J2_13") (pinfunction "PG3_J2_13") (pintype "passive"))
    )
    (net (code "109") (name "unconnected-(M1-PG6-PadJ2_15)") (class "Default")
      (node (ref "M1") (pin "J2_15") (pinfunction "PG6_J2_15") (pintype "passive"))
    )
    (net (code "110") (name "unconnected-(M1-PG11-PadJ2_35)") (class "Default")
      (node (ref "M1") (pin "J2_35") (pinfunction "PG11_J2_35") (pintype "passive"))
    )
    (net (code "111") (name "unconnected-(M1-PH2-PadJ1_5)") (class "Default")
      (node (ref "M1") (pin "J1_5") (pinfunction "PH2_J1_5") (pintype "passive"))
    )
    (net (code "112") (name "unconnected-(M1-PH3-PadJ1_6)") (class "Default")
      (node (ref "M1") (pin "J1_6") (pinfunction "PH3_J1_6") (pintype "passive"))
    )
    (net (code "113") (name "unconnected-(M1-PH7-PadJ2_9)") (class "Default")
      (node (ref "M1") (pin "J2_9") (pinfunction "PH7_J2_9") (pintype "passive"))
    )
    (net (code "114") (name "unconnected-(M1-PH9-PadJ2_10)") (class "Default")
      (node (ref "M1") (pin "J2_10") (pinfunction "PH9_J2_10") (pintype "passive"))
    )
    (net (code "115") (name "unconnected-(M1-PH10-PadJ2_11)") (class "Default")
      (node (ref "M1") (pin "J2_11") (pinfunction "PH10_J2_11") (pintype "passive"))
    )
    (net (code "116") (name "unconnected-(M1-PH11-PadJ2_12)") (class "Default")
      (node (ref "M1") (pin "J2_12") (pinfunction "PH11_J2_12") (pintype "passive"))
    )
    (net (code "117") (name "unconnected-(M1-PH12-PadJ2_24)") (class "Default")
      (node (ref "M1") (pin "J2_24") (pinfunction "PH12_J2_24") (pintype "passive"))
    )
    (net (code "118") (name "unconnected-(M1-PH13-PadJ2_30)") (class "Default")
      (node (ref "M1") (pin "J2_30") (pinfunction "PH13_J2_30") (pintype "passive"))
    )
    (net (code "119") (name "unconnected-(M1-PH14-PadJ2_29)") (class "Default")
      (node (ref "M1") (pin "J2_29") (pinfunction "PH14_J2_29") (pintype "passive"))
    )
    (net (code "120") (name "unconnected-(M1-PH15-PadJ2_28)") (class "Default")
      (node (ref "M1") (pin "J2_28") (pinfunction "PH15_J2_28") (pintype "passive"))
    )
    (net (code "121") (name "unconnected-(M1-PI0-PadJ2_34)") (class "Default")
      (node (ref "M1") (pin "J2_34") (pinfunction "PI0_J2_34") (pintype "passive"))
    )
    (net (code "122") (name "unconnected-(M1-PI1-PadJ2_33)") (class "Default")
      (node (ref "M1") (pin "J2_33") (pinfunction "PI1_J2_33") (pintype "passive"))
    )
    (net (code "123") (name "unconnected-(M1-PI2-PadJ2_32)") (class "Default")
      (node (ref "M1") (pin "J2_32") (pinfunction "PI2_J2_32") (pintype "passive"))
    )
    (net (code "124") (name "unconnected-(M1-PI3-PadJ2_41)") (class "Default")
      (node (ref "M1") (pin "J2_41") (pinfunction "PI3_J2_41") (pintype "passive"))
    )
    (net (code "125") (name "unconnected-(M1-PI4-PadJ2_36)") (class "Default")
      (node (ref "M1") (pin "J2_36") (pinfunction "PI4_J2_36") (pintype "passive"))
    )
    (net (code "126") (name "unconnected-(M1-PI5-PadJ2_37)") (class "Default")
      (node (ref "M1") (pin "J2_37") (pinfunction "PI5_J2_37") (pintype "passive"))
    )
    (net (code "127") (name "unconnected-(M1-PI6-PadJ2_38)") (class "Default")
      (node (ref "M1") (pin "J2_38") (pinfunction "PI6_J2_38") (pintype "passive"))
    )
    (net (code "128") (name "unconnected-(M1-PI7-PadJ2_39)") (class "Default")
      (node (ref "M1") (pin "J2_39") (pinfunction "PI7_J2_39") (pintype "passive"))
    )
    (net (code "129") (name "unconnected-(M1-PI8-PadJ2_40)") (class "Default")
      (node (ref "M1") (pin "J2_40") (pinfunction "PI8_J2_40") (pintype "passive"))
    )
    (net (code "130") (name "unconnected-(M1-VBAT-PadJ1_29)") (class "Default")
      (node (ref "M1") (pin "J1_29") (pinfunction "VBAT_J1_29") (pintype "passive"))
    )
    (net (code "131") (name "unconnected-(SD_CARD-CD-Pad10)") (class "Default")
      (node (ref "SD_CARD") (pin "10") (pinfunction "CD_10") (pintype "passive"))
    )
    (net (code "132") (name "unconnected-(SD_CARD-GND-Pad11)") (class "Default")
      (node (ref "SD_CARD") (pin "11") (pinfunction "GND_11") (pintype "passive"))
    )
    (net (code "133") (name "unconnected-(SD_CARD-WP-Pad12)") (class "Default")
      (node (ref "SD_CARD") (pin "12") (pinfunction "WP_12") (pintype "passive"))
    )
    (net (code "134") (name "unconnected-(U2-AUX_CL-Pad7)") (class "Default")
      (node (ref "U2") (pin "7") (pinfunction "AUX_CL_7") (pintype "passive"))
    )
    (net (code "135") (name "unconnected-(U2-AUX_DA-Pad21)") (class "Default")
      (node (ref "U2") (pin "21") (pinfunction "AUX_DA_21") (pintype "passive"))
    )
    (net (code "136") (name "unconnected-(U2-NC-Pad2)") (class "Default")
      (node (ref "U2") (pin "2") (pinfunction "NC_2") (pintype "passive"))
    )
    (net (code "137") (name "unconnected-(U2-NC-Pad3)") (class "Default")
      (node (ref "U2") (pin "3") (pinfunction "NC_3") (pintype "passive"))
    )
    (net (code "138") (name "unconnected-(U2-NC-Pad4)") (class "Default")
      (node (ref "U2") (pin "4") (pinfunction "NC_4") (pintype "passive"))
    )
    (net (code "139") (name "unconnected-(U2-NC-Pad5)") (class "Default")
      (node (ref "U2") (pin "5") (pinfunction "NC_5") (pintype "passive"))
    )
    (net (code "140") (name "unconnected-(U2-NC-Pad6)") (class "Default")
      (node (ref "U2") (pin "6") (pinfunction "NC_6") (pintype "passive"))
    )
    (net (code "141") (name "unconnected-(U2-NC-Pad14)") (class "Default")
      (node (ref "U2") (pin "14") (pinfunction "NC_14") (pintype "passive"))
    )
    (net (code "142") (name "unconnected-(U2-NC-Pad15)") (class "Default")
      (node (ref "U2") (pin "15") (pinfunction "NC_15") (pintype "passive"))
    )
    (net (code "143") (name "unconnected-(U2-NC-Pad16)") (class "Default")
      (node (ref "U2") (pin "16") (pinfunction "NC_16") (pintype "passive"))
    )
    (net (code "144") (name "unconnected-(U2-NC-Pad17)") (class "Default")
      (node (ref "U2") (pin "17") (pinfunction "NC_17") (pintype "passive"))
    )
    (net (code "145") (name "unconnected-(U2-RESV-Pad19)") (class "Default")
      (node (ref "U2") (pin "19") (pinfunction "RESV_19") (pintype "passive"))
    )
    (net (code "146") (name "unconnected-(U2-nCS-Pad22)") (class "Default")
      (node (ref "U2") (pin "22") (pinfunction "nCS_22") (pintype "passive"))
    )
  )
)
